# Control_module.net
KiCad netlist of a schematic drawn in Altium Designer
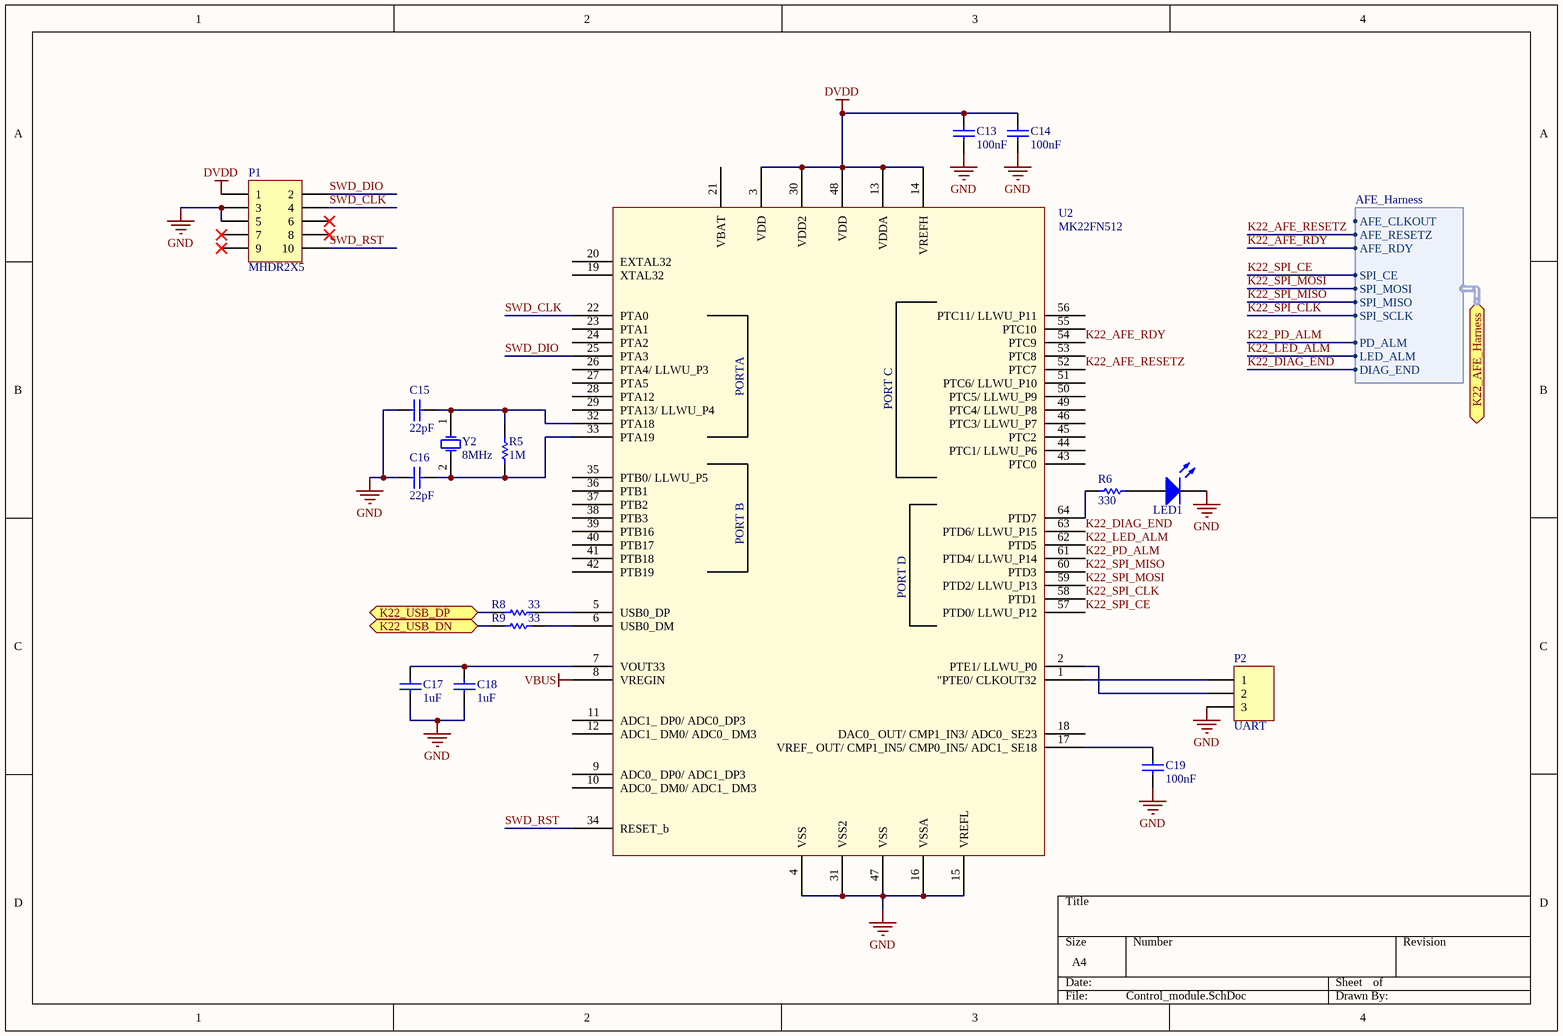
[diagram p0: Control_module.SchDoc]

(export (version "E")
  (design (tool "Eeschema 10.0.6"))
  (components
    (comp (ref "C13")
      (value "100nF")
      (footprint "6-0805_M")
      (description "Capacitor")
      (fields (field (name "Comment") "Cap") (field (name "PUBLISHER") "Altium Limited"))
      (libsource (lib "Miscellaneous Devices") (part "Cap"))
    )
    (comp (ref "C14")
      (value "100nF")
      (footprint "6-0805_M")
      (description "Capacitor")
      (fields (field (name "Comment") "Cap") (field (name "PUBLISHER") "Altium Limited"))
      (libsource (lib "Miscellaneous Devices") (part "Cap"))
    )
    (comp (ref "C15")
      (value "22pF")
      (footprint "6-0805_M")
      (description "Capacitor")
      (fields (field (name "Comment") "Cap") (field (name "PUBLISHER") "Altium Limited"))
      (libsource (lib "Miscellaneous Devices") (part "Cap"))
    )
    (comp (ref "C16")
      (value "22pF")
      (footprint "6-0805_M")
      (description "Capacitor")
      (fields (field (name "Comment") "Cap") (field (name "PUBLISHER") "Altium Limited"))
      (libsource (lib "Miscellaneous Devices") (part "Cap"))
    )
    (comp (ref "C17")
      (value "1uF")
      (footprint "6-0805_M")
      (description "Capacitor")
      (fields (field (name "Comment") "Cap") (field (name "PUBLISHER") "Altium Limited"))
      (libsource (lib "Miscellaneous Devices") (part "Cap"))
    )
    (comp (ref "C18")
      (value "1uF")
      (footprint "6-0805_M")
      (description "Capacitor")
      (fields (field (name "Comment") "Cap") (field (name "PUBLISHER") "Altium Limited"))
      (libsource (lib "Miscellaneous Devices") (part "Cap"))
    )
    (comp (ref "C19")
      (value "100nF")
      (footprint "6-0805_M")
      (description "Capacitor")
      (fields (field (name "Comment") "Cap") (field (name "PUBLISHER") "Altium Limited"))
      (libsource (lib "Miscellaneous Devices") (part "Cap"))
    )
    (comp (ref "LED1")
      (value "LED0")
      (footprint "6-0805_M")
      (description "Typical INFRARED GaAs LED")
      (fields (field (name "PUBLISHER") "Altium Limited"))
      (libsource (lib "Miscellaneous Devices") (part "LED0"))
    )
    (comp (ref "P1")
      (value "MHDR2X5")
      (footprint "MHDR2X5")
      (description "Header, 5-Pin, Dual row")
      (fields (field (name "PUBLISHER") "Altium Limited"))
      (libsource (lib "Miscellaneous Connectors") (part "MHDR2X5"))
    )
    (comp (ref "P2")
      (value "UART")
      (footprint "HDR1X3")
      (description "Header, 3-Pin")
      (fields (field (name "PUBLISHER") "Altium Limited"))
      (libsource (lib "Miscellaneous Connectors") (part "Header 3"))
    )
    (comp (ref "R5")
      (value "1M")
      (footprint "6-0805_M")
      (description "Resistor")
      (fields (field (name "Comment") "Res1") (field (name "PUBLISHER") "Altium Limited"))
      (libsource (lib "Miscellaneous Devices") (part "Res1"))
    )
    (comp (ref "R6")
      (value "330")
      (footprint "6-0805_M")
      (description "Resistor")
      (fields (field (name "Comment") "Res1") (field (name "PUBLISHER") "Altium Limited"))
      (libsource (lib "Miscellaneous Devices") (part "Res1"))
    )
    (comp (ref "R8")
      (value "33")
      (footprint "6-0805_M")
      (description "Resistor")
      (fields (field (name "Comment") "Res1") (field (name "PUBLISHER") "Altium Limited"))
      (libsource (lib "Miscellaneous Devices") (part "Res1"))
    )
    (comp (ref "R9")
      (value "33")
      (footprint "6-0805_M")
      (description "Resistor")
      (fields (field (name "Comment") "Res1") (field (name "PUBLISHER") "Altium Limited"))
      (libsource (lib "Miscellaneous Devices") (part "Res1"))
    )
    (comp (ref "U2")
      (value "MK22FN512")
      (footprint "TQFP64_M")
      (description "120 MHz Cortex-M4 Based Microcontroller with FPU")
      (libsource (lib "MK22FN512") (part "MK22FN512"))
    )
    (comp (ref "Y2")
      (value "8MHz")
      (footprint "Crystal SMD")
      (description "Crystal Oscillator")
      (fields (field (name "PUBLISHER") "Altium Limited"))
      (libsource (lib "Miscellaneous Devices") (part "XTAL"))
    )
  )
  (nets
    (net (code "2") (name "/K22_AFE_RDY") (class "Default")
      (node (ref "U2") (pin "54") (pinfunction "PTC9_54") (pintype "passive"))
    )
    (net (code "3") (name "/K22_AFE_RESETZ") (class "Default")
      (node (ref "U2") (pin "52") (pinfunction "PTC7_52") (pintype "passive"))
    )
    (net (code "4") (name "/K22_DIAG_END") (class "Default")
      (node (ref "U2") (pin "63") (pinfunction "PTD6/_LLWU_P15_63") (pintype "passive"))
    )
    (net (code "5") (name "/K22_LED_ALM") (class "Default")
      (node (ref "U2") (pin "62") (pinfunction "PTD5_62") (pintype "passive"))
    )
    (net (code "6") (name "/K22_PD_ALM") (class "Default")
      (node (ref "U2") (pin "61") (pinfunction "PTD4/_LLWU_P14_61") (pintype "passive"))
    )
    (net (code "7") (name "/K22_SPI_CE") (class "Default")
      (node (ref "U2") (pin "57") (pinfunction "PTD0/_LLWU_P12_57") (pintype "passive"))
    )
    (net (code "8") (name "/K22_SPI_CLK") (class "Default")
      (node (ref "U2") (pin "58") (pinfunction "PTD1_58") (pintype "passive"))
    )
    (net (code "9") (name "/K22_SPI_MISO") (class "Default")
      (node (ref "U2") (pin "60") (pinfunction "PTD3_60") (pintype "passive"))
    )
    (net (code "10") (name "/K22_SPI_MOSI") (class "Default")
      (node (ref "U2") (pin "59") (pinfunction "PTD2/_LLWU_P13_59") (pintype "passive"))
    )
    (net (code "11") (name "/K22_USB_DN") (class "Default")
      (node (ref "R9") (pin "1") (pinfunction "1_1") (pintype "passive"))
    )
    (net (code "12") (name "/K22_USB_DP") (class "Default")
      (node (ref "R8") (pin "1") (pinfunction "1_1") (pintype "passive"))
    )
    (net (code "13") (name "/SWD_CLK") (class "Default")
      (node (ref "P1") (pin "4") (pinfunction "4_4") (pintype "passive"))
      (node (ref "U2") (pin "22") (pinfunction "PTA0_22") (pintype "passive"))
    )
    (net (code "14") (name "/SWD_DIO") (class "Default")
      (node (ref "P1") (pin "2") (pinfunction "2_2") (pintype "passive"))
      (node (ref "U2") (pin "25") (pinfunction "PTA3_25") (pintype "passive"))
    )
    (net (code "15") (name "/SWD_RST") (class "Default")
      (node (ref "P1") (pin "10") (pinfunction "10_10") (pintype "passive"))
      (node (ref "U2") (pin "34") (pinfunction "RESET_b_34") (pintype "passive"))
    )
    (net (code "17") (name "DVDD") (class "Default")
      (node (ref "C13") (pin "1") (pinfunction "1_1") (pintype "passive"))
      (node (ref "C14") (pin "1") (pinfunction "1_1") (pintype "passive"))
      (node (ref "P1") (pin "1") (pinfunction "1_1") (pintype "passive"))
      (node (ref "U2") (pin "13") (pinfunction "VDDA_13") (pintype "passive"))
      (node (ref "U2") (pin "14") (pinfunction "VREFH_14") (pintype "passive"))
      (node (ref "U2") (pin "3") (pinfunction "VDD_3") (pintype "passive"))
      (node (ref "U2") (pin "30") (pinfunction "VDD2_30") (pintype "passive"))
      (node (ref "U2") (pin "48") (pinfunction "VDD_48") (pintype "passive"))
    )
    (net (code "18") (name "GND") (class "Default")
      (node (ref "C13") (pin "2") (pinfunction "2_2") (pintype "passive"))
      (node (ref "C14") (pin "2") (pinfunction "2_2") (pintype "passive"))
      (node (ref "C15") (pin "1") (pinfunction "1_1") (pintype "passive"))
      (node (ref "C16") (pin "1") (pinfunction "1_1") (pintype "passive"))
      (node (ref "C17") (pin "1") (pinfunction "1_1") (pintype "passive"))
      (node (ref "C18") (pin "1") (pinfunction "1_1") (pintype "passive"))
      (node (ref "C19") (pin "1") (pinfunction "1_1") (pintype "passive"))
      (node (ref "LED1") (pin "2") (pinfunction "K_2") (pintype "passive"))
      (node (ref "P1") (pin "3") (pinfunction "3_3") (pintype "passive"))
      (node (ref "P1") (pin "5") (pinfunction "5_5") (pintype "passive"))
      (node (ref "P2") (pin "3") (pinfunction "3_3") (pintype "passive"))
      (node (ref "U2") (pin "15") (pinfunction "VREFL_15") (pintype "passive"))
      (node (ref "U2") (pin "16") (pinfunction "VSSA_16") (pintype "passive"))
      (node (ref "U2") (pin "31") (pinfunction "VSS2_31") (pintype "passive"))
      (node (ref "U2") (pin "4") (pinfunction "VSS_4") (pintype "passive"))
      (node (ref "U2") (pin "47") (pinfunction "VSS_47") (pintype "passive"))
    )
    (net (code "19") (name "Net-(LED1-A)") (class "Default")
      (node (ref "LED1") (pin "1") (pinfunction "A_1") (pintype "passive"))
      (node (ref "R6") (pin "2") (pinfunction "2_2") (pintype "passive"))
    )
    (net (code "20") (name "Net-(U2-\"PTE0{slash}_CLKOUT32)") (class "Default")
      (node (ref "P2") (pin "1") (pinfunction "1_1") (pintype "passive"))
      (node (ref "U2") (pin "1") (pinfunction "\"PTE0/_CLKOUT32_1") (pintype "passive"))
    )
    (net (code "21") (name "Net-(U2-PTA18)") (class "Default")
      (node (ref "C15") (pin "2") (pinfunction "2_2") (pintype "passive"))
      (node (ref "R5") (pin "1") (pinfunction "1_1") (pintype "passive"))
      (node (ref "U2") (pin "32") (pinfunction "PTA18_32") (pintype "passive"))
      (node (ref "Y2") (pin "1") (pinfunction "OSC1_1") (pintype "passive"))
    )
    (net (code "22") (name "Net-(U2-PTA19)") (class "Default")
      (node (ref "C16") (pin "2") (pinfunction "2_2") (pintype "passive"))
      (node (ref "R5") (pin "2") (pinfunction "2_2") (pintype "passive"))
      (node (ref "U2") (pin "33") (pinfunction "PTA19_33") (pintype "passive"))
      (node (ref "Y2") (pin "2") (pinfunction "OSC2_2") (pintype "passive"))
    )
    (net (code "23") (name "Net-(U2-PTD7)") (class "Default")
      (node (ref "R6") (pin "1") (pinfunction "1_1") (pintype "passive"))
      (node (ref "U2") (pin "64") (pinfunction "PTD7_64") (pintype "passive"))
    )
    (net (code "24") (name "Net-(U2-PTE1{slash}_LLWU_P0)") (class "Default")
      (node (ref "P2") (pin "2") (pinfunction "2_2") (pintype "passive"))
      (node (ref "U2") (pin "2") (pinfunction "PTE1/_LLWU_P0_2") (pintype "passive"))
    )
    (net (code "25") (name "Net-(U2-USB0_DM)") (class "Default")
      (node (ref "R9") (pin "2") (pinfunction "2_2") (pintype "passive"))
      (node (ref "U2") (pin "6") (pinfunction "USB0_DM_6") (pintype "passive"))
    )
    (net (code "26") (name "Net-(U2-USB0_DP)") (class "Default")
      (node (ref "R8") (pin "2") (pinfunction "2_2") (pintype "passive"))
      (node (ref "U2") (pin "5") (pinfunction "USB0_DP_5") (pintype "passive"))
    )
    (net (code "27") (name "Net-(U2-VOUT33)") (class "Default")
      (node (ref "C17") (pin "2") (pinfunction "2_2") (pintype "passive"))
      (node (ref "C18") (pin "2") (pinfunction "2_2") (pintype "passive"))
      (node (ref "U2") (pin "7") (pinfunction "VOUT33_7") (pintype "passive"))
    )
    (net (code "28") (name "Net-(U2-VREF__OUT{slash}_CMP1_IN5{slash}_CMP0_IN5{slash}_ADC1__SE18)") (class "Default")
      (node (ref "C19") (pin "2") (pinfunction "2_2") (pintype "passive"))
      (node (ref "U2") (pin "17") (pinfunction "VREF__OUT/_CMP1_IN5/_CMP0_IN5/_ADC1__SE18_17") (pintype "passive"))
    )
    (net (code "29") (name "VBUS") (class "Default")
      (node (ref "U2") (pin "8") (pinfunction "VREGIN_8") (pintype "passive"))
    )
    (net (code "30") (name "unconnected-(P1-Pad6)") (class "Default")
      (node (ref "P1") (pin "6") (pinfunction "6_6") (pintype "passive+no_connect"))
    )
    (net (code "31") (name "unconnected-(P1-Pad7)") (class "Default")
      (node (ref "P1") (pin "7") (pinfunction "7_7") (pintype "passive+no_connect"))
    )
    (net (code "32") (name "unconnected-(P1-Pad8)") (class "Default")
      (node (ref "P1") (pin "8") (pinfunction "8_8") (pintype "passive+no_connect"))
    )
    (net (code "33") (name "unconnected-(P1-Pad9)") (class "Default")
      (node (ref "P1") (pin "9") (pinfunction "9_9") (pintype "passive+no_connect"))
    )
    (net (code "34") (name "unconnected-(U2-ADC0__DM0{slash}_ADC1__DM3-Pad10)") (class "Default")
      (node (ref "U2") (pin "10") (pinfunction "ADC0__DM0/_ADC1__DM3_10") (pintype "passive"))
    )
    (net (code "35") (name "unconnected-(U2-ADC0__DP0{slash}_ADC1_DP3-Pad9)") (class "Default")
      (node (ref "U2") (pin "9") (pinfunction "ADC0__DP0/_ADC1_DP3_9") (pintype "passive"))
    )
    (net (code "36") (name "unconnected-(U2-ADC1__DM0{slash}_ADC0__DM3-Pad12)") (class "Default")
      (node (ref "U2") (pin "12") (pinfunction "ADC1__DM0/_ADC0__DM3_12") (pintype "passive"))
    )
    (net (code "37") (name "unconnected-(U2-ADC1__DP0{slash}_ADC0_DP3-Pad11)") (class "Default")
      (node (ref "U2") (pin "11") (pinfunction "ADC1__DP0/_ADC0_DP3_11") (pintype "passive"))
    )
    (net (code "38") (name "unconnected-(U2-DAC0__OUT{slash}_CMP1_IN3{slash}_ADC0__SE23-Pad18)") (class "Default")
      (node (ref "U2") (pin "18") (pinfunction "DAC0__OUT/_CMP1_IN3/_ADC0__SE23_18") (pintype "passive"))
    )
    (net (code "39") (name "unconnected-(U2-EXTAL32-Pad20)") (class "Default")
      (node (ref "U2") (pin "20") (pinfunction "EXTAL32_20") (pintype "passive"))
    )
    (net (code "40") (name "unconnected-(U2-PTA1-Pad23)") (class "Default")
      (node (ref "U2") (pin "23") (pinfunction "PTA1_23") (pintype "passive"))
    )
    (net (code "41") (name "unconnected-(U2-PTA2-Pad24)") (class "Default")
      (node (ref "U2") (pin "24") (pinfunction "PTA2_24") (pintype "passive"))
    )
    (net (code "42") (name "unconnected-(U2-PTA4{slash}_LLWU_P3-Pad26)") (class "Default")
      (node (ref "U2") (pin "26") (pinfunction "PTA4/_LLWU_P3_26") (pintype "passive"))
    )
    (net (code "43") (name "unconnected-(U2-PTA5-Pad27)") (class "Default")
      (node (ref "U2") (pin "27") (pinfunction "PTA5_27") (pintype "passive"))
    )
    (net (code "44") (name "unconnected-(U2-PTA12-Pad28)") (class "Default")
      (node (ref "U2") (pin "28") (pinfunction "PTA12_28") (pintype "passive"))
    )
    (net (code "45") (name "unconnected-(U2-PTA13{slash}_LLWU_P4-Pad29)") (class "Default")
      (node (ref "U2") (pin "29") (pinfunction "PTA13/_LLWU_P4_29") (pintype "passive"))
    )
    (net (code "46") (name "unconnected-(U2-PTB0{slash}_LLWU_P5-Pad35)") (class "Default")
      (node (ref "U2") (pin "35") (pinfunction "PTB0/_LLWU_P5_35") (pintype "passive"))
    )
    (net (code "47") (name "unconnected-(U2-PTB1-Pad36)") (class "Default")
      (node (ref "U2") (pin "36") (pinfunction "PTB1_36") (pintype "passive"))
    )
    (net (code "48") (name "unconnected-(U2-PTB2-Pad37)") (class "Default")
      (node (ref "U2") (pin "37") (pinfunction "PTB2_37") (pintype "passive"))
    )
    (net (code "49") (name "unconnected-(U2-PTB3-Pad38)") (class "Default")
      (node (ref "U2") (pin "38") (pinfunction "PTB3_38") (pintype "passive"))
    )
    (net (code "50") (name "unconnected-(U2-PTB16-Pad39)") (class "Default")
      (node (ref "U2") (pin "39") (pinfunction "PTB16_39") (pintype "passive"))
    )
    (net (code "51") (name "unconnected-(U2-PTB17-Pad40)") (class "Default")
      (node (ref "U2") (pin "40") (pinfunction "PTB17_40") (pintype "passive"))
    )
    (net (code "52") (name "unconnected-(U2-PTB18-Pad41)") (class "Default")
      (node (ref "U2") (pin "41") (pinfunction "PTB18_41") (pintype "passive"))
    )
    (net (code "53") (name "unconnected-(U2-PTB19-Pad42)") (class "Default")
      (node (ref "U2") (pin "42") (pinfunction "PTB19_42") (pintype "passive"))
    )
    (net (code "54") (name "unconnected-(U2-PTC0-Pad43)") (class "Default")
      (node (ref "U2") (pin "43") (pinfunction "PTC0_43") (pintype "passive"))
    )
    (net (code "55") (name "unconnected-(U2-PTC1{slash}_LLWU_P6-Pad44)") (class "Default")
      (node (ref "U2") (pin "44") (pinfunction "PTC1/_LLWU_P6_44") (pintype "passive"))
    )
    (net (code "56") (name "unconnected-(U2-PTC2-Pad45)") (class "Default")
      (node (ref "U2") (pin "45") (pinfunction "PTC2_45") (pintype "passive"))
    )
    (net (code "57") (name "unconnected-(U2-PTC3{slash}_LLWU_P7-Pad46)") (class "Default")
      (node (ref "U2") (pin "46") (pinfunction "PTC3/_LLWU_P7_46") (pintype "passive"))
    )
    (net (code "58") (name "unconnected-(U2-PTC4{slash}_LLWU_P8-Pad49)") (class "Default")
      (node (ref "U2") (pin "49") (pinfunction "PTC4/_LLWU_P8_49") (pintype "passive"))
    )
    (net (code "59") (name "unconnected-(U2-PTC5{slash}_LLWU_P9-Pad50)") (class "Default")
      (node (ref "U2") (pin "50") (pinfunction "PTC5/_LLWU_P9_50") (pintype "passive"))
    )
    (net (code "60") (name "unconnected-(U2-PTC6{slash}_LLWU_P10-Pad51)") (class "Default")
      (node (ref "U2") (pin "51") (pinfunction "PTC6/_LLWU_P10_51") (pintype "passive"))
    )
    (net (code "61") (name "unconnected-(U2-PTC8-Pad53)") (class "Default")
      (node (ref "U2") (pin "53") (pinfunction "PTC8_53") (pintype "passive"))
    )
    (net (code "62") (name "unconnected-(U2-PTC10-Pad55)") (class "Default")
      (node (ref "U2") (pin "55") (pinfunction "PTC10_55") (pintype "passive"))
    )
    (net (code "63") (name "unconnected-(U2-PTC11{slash}_LLWU_P11-Pad56)") (class "Default")
      (node (ref "U2") (pin "56") (pinfunction "PTC11/_LLWU_P11_56") (pintype "passive"))
    )
    (net (code "64") (name "unconnected-(U2-VBAT-Pad21)") (class "Default")
      (node (ref "U2") (pin "21") (pinfunction "VBAT_21") (pintype "passive"))
    )
    (net (code "65") (name "unconnected-(U2-XTAL32-Pad19)") (class "Default")
      (node (ref "U2") (pin "19") (pinfunction "XTAL32_19") (pintype "passive"))
    )
  )
)
